# astroCACTUS.net
KiCad netlist of a schematic drawn in EAGLE
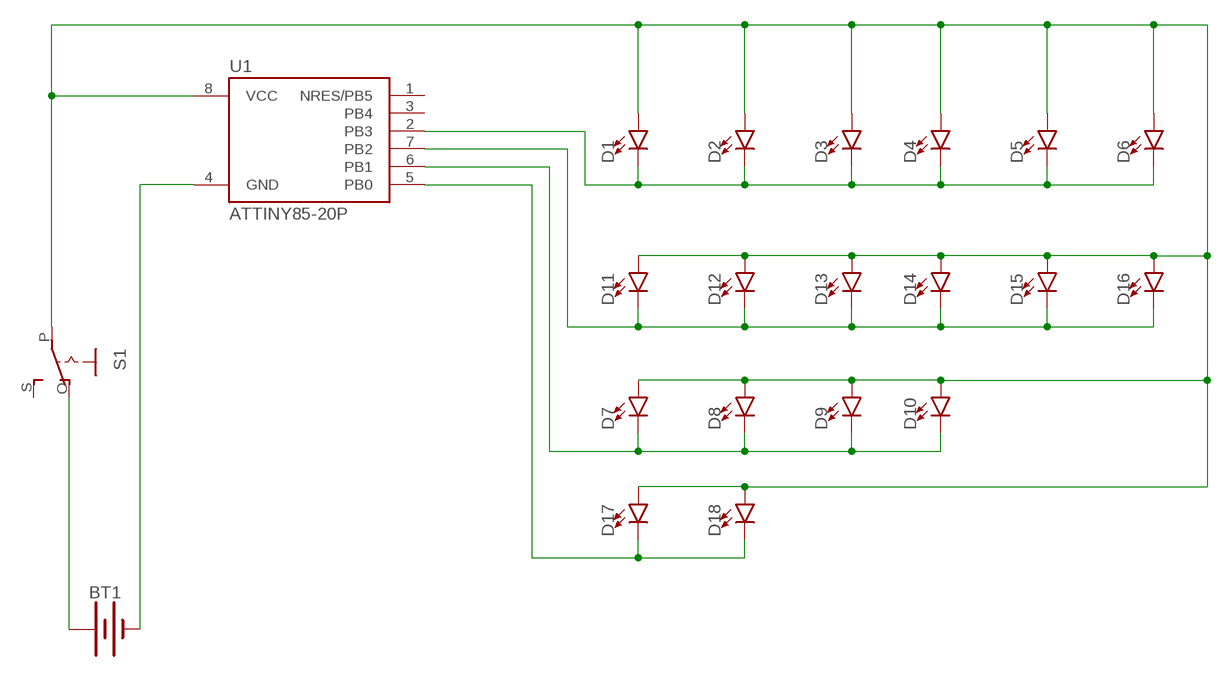
[diagram p0: schematic, sheet 1]

(export (version "E")
  (design (tool "Eeschema 10.0.6"))
  (components
    (comp (ref "BT1")
      (value "BATTERY-20MM_PTH")
      (footprint "eagle-import:BATTCOM_20MM_PTH")
      (libsource (lib "eagle-import") (part "BATTERY-20MM_PTH"))
    )
    (comp (ref "D1")
      (value "LED3MM")
      (footprint "eagle-import:LED_3MM")
      (libsource (lib "eagle-import") (part "LED3MM"))
    )
    (comp (ref "D2")
      (value "LED3MM")
      (footprint "eagle-import:LED_3MM")
      (libsource (lib "eagle-import") (part "LED3MM"))
    )
    (comp (ref "D3")
      (value "LED3MM")
      (footprint "eagle-import:LED_3MM")
      (libsource (lib "eagle-import") (part "LED3MM"))
    )
    (comp (ref "D4")
      (value "LED3MM")
      (footprint "eagle-import:LED_3MM")
      (libsource (lib "eagle-import") (part "LED3MM"))
    )
    (comp (ref "D5")
      (value "LED3MM")
      (footprint "eagle-import:LED_3MM")
      (libsource (lib "eagle-import") (part "LED3MM"))
    )
    (comp (ref "D6")
      (value "LED3MM")
      (footprint "eagle-import:LED_3MM")
      (libsource (lib "eagle-import") (part "LED3MM"))
    )
    (comp (ref "D7")
      (value "LED3MM")
      (footprint "eagle-import:LED_3MM")
      (libsource (lib "eagle-import") (part "LED3MM"))
    )
    (comp (ref "D8")
      (value "LED3MM")
      (footprint "eagle-import:LED_3MM")
      (libsource (lib "eagle-import") (part "LED3MM"))
    )
    (comp (ref "D9")
      (value "LED3MM")
      (footprint "eagle-import:LED_3MM")
      (libsource (lib "eagle-import") (part "LED3MM"))
    )
    (comp (ref "D10")
      (value "LED3MM")
      (footprint "eagle-import:LED_3MM")
      (libsource (lib "eagle-import") (part "LED3MM"))
    )
    (comp (ref "D11")
      (value "LED3MM")
      (footprint "eagle-import:LED_3MM")
      (libsource (lib "eagle-import") (part "LED3MM"))
    )
    (comp (ref "D12")
      (value "LED3MM")
      (footprint "eagle-import:LED_3MM")
      (libsource (lib "eagle-import") (part "LED3MM"))
    )
    (comp (ref "D13")
      (value "LED3MM")
      (footprint "eagle-import:LED_3MM")
      (libsource (lib "eagle-import") (part "LED3MM"))
    )
    (comp (ref "D14")
      (value "LED3MM")
      (footprint "eagle-import:LED_3MM")
      (libsource (lib "eagle-import") (part "LED3MM"))
    )
    (comp (ref "D15")
      (value "LED3MM")
      (footprint "eagle-import:LED_3MM")
      (libsource (lib "eagle-import") (part "LED3MM"))
    )
    (comp (ref "D16")
      (value "LED3MM")
      (footprint "eagle-import:LED_3MM")
      (libsource (lib "eagle-import") (part "LED3MM"))
    )
    (comp (ref "D17")
      (value "LED3MM")
      (footprint "eagle-import:LED_3MM")
      (libsource (lib "eagle-import") (part "LED3MM"))
    )
    (comp (ref "D18")
      (value "LED3MM")
      (footprint "eagle-import:LED_3MM")
      (libsource (lib "eagle-import") (part "LED3MM"))
    )
    (comp (ref "S1")
      (value "EG1218S")
      (footprint "eagle-import:EG1218")
      (libsource (lib "eagle-import") (part "EG1218S"))
    )
    (comp (ref "U1")
      (value "ATTINY85-20P")
      (footprint "eagle-import:PDIP08_300MIL")
      (libsource (lib "eagle-import") (part "ATTINY85P-20"))
    )
  )
  (nets
    (net (code "1") (name "Net-(BT1-+)") (class "Default")
      (node (ref "BT1") (pin "1") (pinfunction "+_1") (pintype "power_in"))
      (node (ref "S1") (pin "O") (pinfunction "O_O") (pintype "passive"))
    )
    (net (code "2") (name "Net-(BT1--)") (class "Default")
      (node (ref "BT1") (pin "2") (pinfunction "-_2") (pintype "power_in"))
      (node (ref "U1") (pin "4") (pinfunction "GND_4") (pintype "power_in"))
    )
    (net (code "3") (name "Net-(D1-C)") (class "Default")
      (node (ref "D1") (pin "K") (pinfunction "C_K") (pintype "passive"))
      (node (ref "D2") (pin "K") (pinfunction "C_K") (pintype "passive"))
      (node (ref "D3") (pin "K") (pinfunction "C_K") (pintype "passive"))
      (node (ref "D4") (pin "K") (pinfunction "C_K") (pintype "passive"))
      (node (ref "D5") (pin "K") (pinfunction "C_K") (pintype "passive"))
      (node (ref "D6") (pin "K") (pinfunction "C_K") (pintype "passive"))
      (node (ref "U1") (pin "2") (pinfunction "PB3_2") (pintype "bidirectional"))
    )
    (net (code "4") (name "Net-(D10-C)") (class "Default")
      (node (ref "D10") (pin "K") (pinfunction "C_K") (pintype "passive"))
      (node (ref "D7") (pin "K") (pinfunction "C_K") (pintype "passive"))
      (node (ref "D8") (pin "K") (pinfunction "C_K") (pintype "passive"))
      (node (ref "D9") (pin "K") (pinfunction "C_K") (pintype "passive"))
      (node (ref "U1") (pin "6") (pinfunction "PB1_6") (pintype "bidirectional"))
    )
    (net (code "5") (name "Net-(D11-C)") (class "Default")
      (node (ref "D11") (pin "K") (pinfunction "C_K") (pintype "passive"))
      (node (ref "D12") (pin "K") (pinfunction "C_K") (pintype "passive"))
      (node (ref "D13") (pin "K") (pinfunction "C_K") (pintype "passive"))
      (node (ref "D14") (pin "K") (pinfunction "C_K") (pintype "passive"))
      (node (ref "D15") (pin "K") (pinfunction "C_K") (pintype "passive"))
      (node (ref "D16") (pin "K") (pinfunction "C_K") (pintype "passive"))
      (node (ref "U1") (pin "7") (pinfunction "PB2_7") (pintype "bidirectional"))
    )
    (net (code "6") (name "Net-(D17-C)") (class "Default")
      (node (ref "D17") (pin "K") (pinfunction "C_K") (pintype "passive"))
      (node (ref "D18") (pin "K") (pinfunction "C_K") (pintype "passive"))
      (node (ref "U1") (pin "5") (pinfunction "PB0_5") (pintype "bidirectional"))
    )
    (net (code "7") (name "Net-(U1-VCC)") (class "Default")
      (node (ref "D1") (pin "A") (pinfunction "A_A") (pintype "passive"))
      (node (ref "D10") (pin "A") (pinfunction "A_A") (pintype "passive"))
      (node (ref "D11") (pin "A") (pinfunction "A_A") (pintype "passive"))
      (node (ref "D12") (pin "A") (pinfunction "A_A") (pintype "passive"))
      (node (ref "D13") (pin "A") (pinfunction "A_A") (pintype "passive"))
      (node (ref "D14") (pin "A") (pinfunction "A_A") (pintype "passive"))
      (node (ref "D15") (pin "A") (pinfunction "A_A") (pintype "passive"))
      (node (ref "D16") (pin "A") (pinfunction "A_A") (pintype "passive"))
      (node (ref "D17") (pin "A") (pinfunction "A_A") (pintype "passive"))
      (node (ref "D18") (pin "A") (pinfunction "A_A") (pintype "passive"))
      (node (ref "D2") (pin "A") (pinfunction "A_A") (pintype "passive"))
      (node (ref "D3") (pin "A") (pinfunction "A_A") (pintype "passive"))
      (node (ref "D4") (pin "A") (pinfunction "A_A") (pintype "passive"))
      (node (ref "D5") (pin "A") (pinfunction "A_A") (pintype "passive"))
      (node (ref "D6") (pin "A") (pinfunction "A_A") (pintype "passive"))
      (node (ref "D7") (pin "A") (pinfunction "A_A") (pintype "passive"))
      (node (ref "D8") (pin "A") (pinfunction "A_A") (pintype "passive"))
      (node (ref "D9") (pin "A") (pinfunction "A_A") (pintype "passive"))
      (node (ref "S1") (pin "P") (pinfunction "P_P") (pintype "passive"))
      (node (ref "U1") (pin "8") (pinfunction "VCC_8") (pintype "power_in"))
    )
    (net (code "8") (name "unconnected-(S1-PadS)") (class "Default")
      (node (ref "S1") (pin "S") (pinfunction "S_S") (pintype "passive"))
    )
    (net (code "9") (name "unconnected-(U1-NRES{slash}PB5-Pad1)") (class "Default")
      (node (ref "U1") (pin "1") (pinfunction "NRES/PB5_1") (pintype "bidirectional"))
    )
    (net (code "10") (name "unconnected-(U1-PB4-Pad3)") (class "Default")
      (node (ref "U1") (pin "3") (pinfunction "PB4_3") (pintype "bidirectional"))
    )
  )
)
